# Connectors.net
KiCad netlist of a schematic drawn in Altium Designer
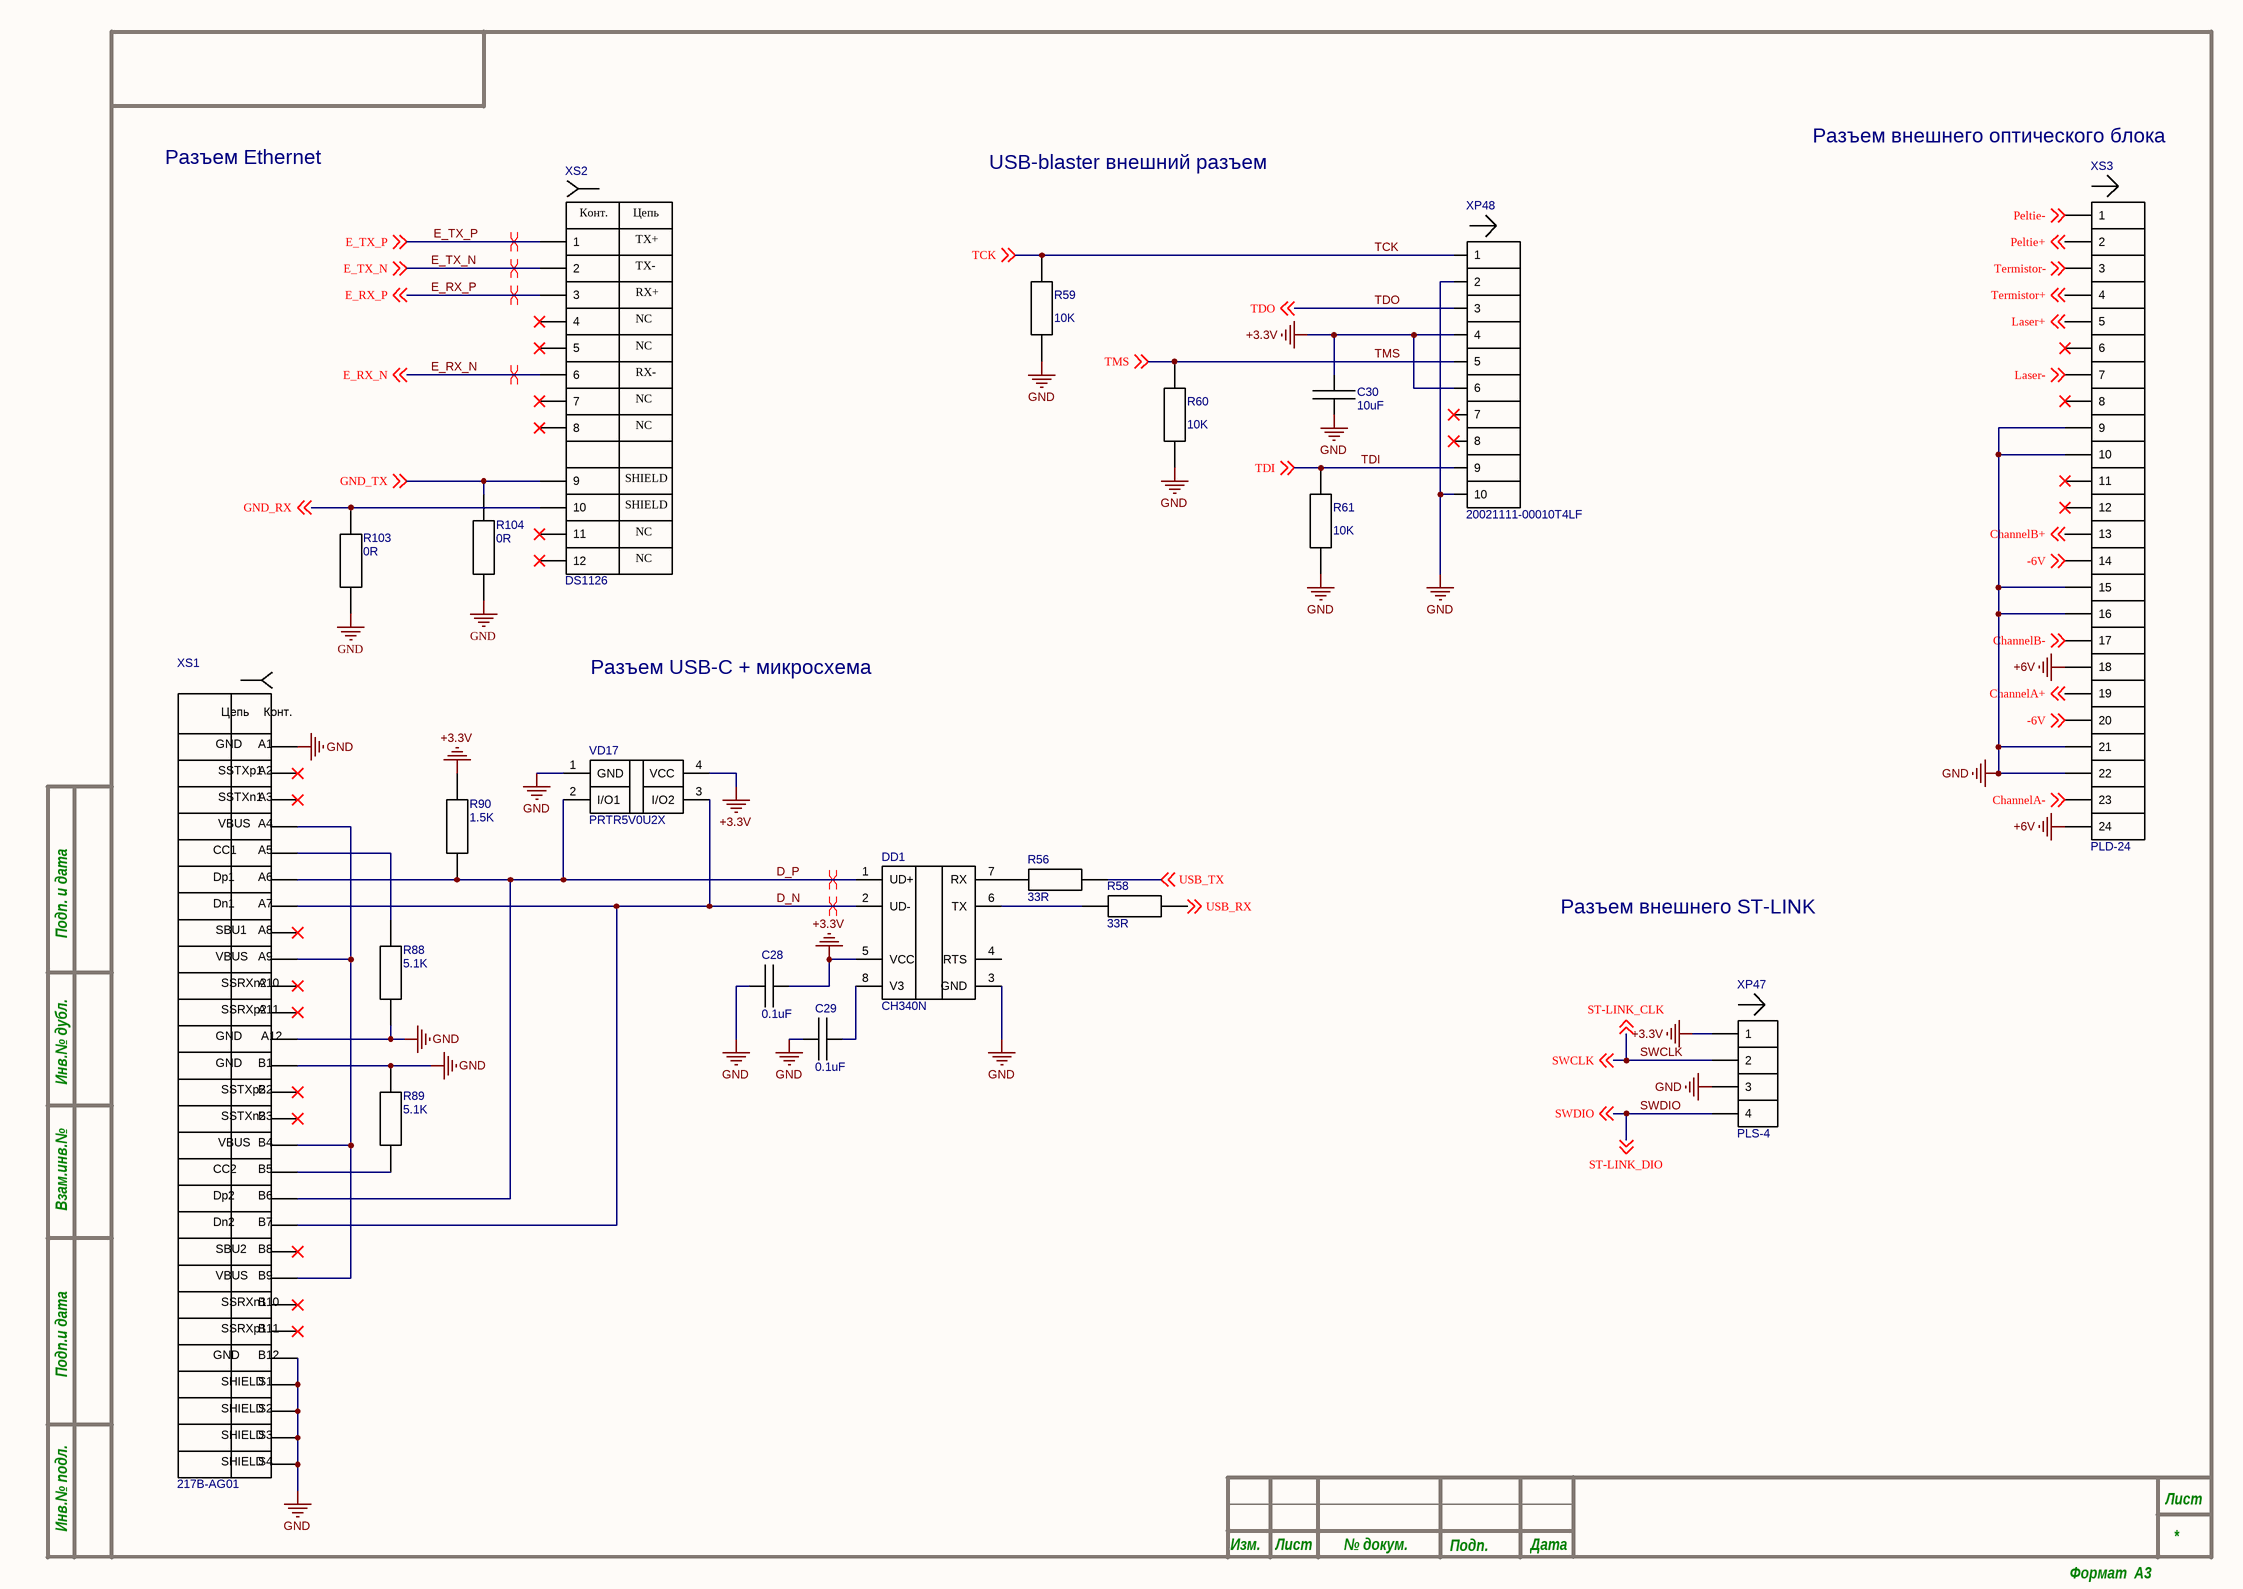
[diagram p0: Connectors — копия.SchDoc]

(export (version "E")
  (design (tool "Eeschema 10.0.6"))
  (components
    (comp (ref "C28")
      (value "0.1uF")
      (footprint "0805C")
      (description "C0805 0.1UF 10% 50V")
      (fields
        (field (name "PART NUMBER") "SMD CAP CER 0.1UF ±10% 50V X7R 0805")
        (field (name "ADDED_BY") "anton@teslatec.ru")
      )
      (libsource (lib "Test_Stand_Pergam") (part "C0805-0.1UF 10% 50V"))
    )
    (comp (ref "C29")
      (value "0.1uF")
      (footprint "0805C")
      (description "C0805 0.1UF 10% 50V")
      (fields
        (field (name "PART NUMBER") "SMD CAP CER 0.1UF ±10% 50V X7R 0805")
        (field (name "ADDED_BY") "anton@teslatec.ru")
      )
      (libsource (lib "Test_Stand_Pergam") (part "C0805-0.1UF 10% 50V"))
    )
    (comp (ref "C30")
      (value "10uF")
      (footprint "0402C")
      (description "C0402-10UF 10% 10V")
      (fields
        (field (name "PART NUMBER") "SMD CAP CER 10UF ±10% 10V X5R 0402")
        (field (name "ADDED_BY") "Rutel@Mail.ru")
      )
      (libsource (lib "Test_Stand_Pergam") (part "C0402-10UF 10% 10V"))
    )
    (comp (ref "DD1")
      (value "CH340N")
      (footprint "SOP8")
      (description "USB to Serial Port Chip CH340, SOP-8")
      (fields (field (name "ADDED_BY") "irdolgopolowa@yandex.ru"))
      (libsource (lib "Test_Stand_Pergam") (part "CH340N"))
    )
    (comp (ref "R56")
      (value "33R")
      (footprint "R0402")
      (description "Resistor SMD 33R 1% 0402")
      (fields
        (field (name "PART NUMBER") "SMD RES 33R OHM 1% ±100ppm/°C 0402")
        (field (name "ADDED_BY") "Rutel@teslatec.ru")
      )
      (libsource (lib "Test_Stand_Pergam") (part "R0402-33R"))
    )
    (comp (ref "R58")
      (value "33R")
      (footprint "R0402")
      (description "Resistor SMD 33R 1% 0402")
      (fields
        (field (name "PART NUMBER") "SMD RES 33R OHM 1% ±100ppm/°C 0402")
        (field (name "ADDED_BY") "Rutel@teslatec.ru")
      )
      (libsource (lib "Test_Stand_Pergam") (part "R0402-33R"))
    )
    (comp (ref "R59")
      (value "10K")
      (footprint "R0402")
      (description "Resistor SMD 10K 1% 0402")
      (fields
        (field (name "PART NUMBER") "SMD RES 10 KOHM 1% ±100ppm/°C 0402")
        (field (name "ADDED_BY") "Rutel@teslatec.ru")
      )
      (libsource (lib "Test_Stand_Pergam") (part "R0402-10K"))
    )
    (comp (ref "R60")
      (value "10K")
      (footprint "R0402")
      (description "Resistor SMD 10K 1% 0402")
      (fields
        (field (name "PART NUMBER") "SMD RES 10 KOHM 1% ±100ppm/°C 0402")
        (field (name "ADDED_BY") "Rutel@teslatec.ru")
      )
      (libsource (lib "Test_Stand_Pergam") (part "R0402-10K"))
    )
    (comp (ref "R61")
      (value "10K")
      (footprint "R0402")
      (description "Resistor SMD 10K 1% 0402")
      (fields
        (field (name "PART NUMBER") "SMD RES 10 KOHM 1% ±100ppm/°C 0402")
        (field (name "ADDED_BY") "Rutel@teslatec.ru")
      )
      (libsource (lib "Test_Stand_Pergam") (part "R0402-10K"))
    )
    (comp (ref "R88")
      (value "5.1K")
      (footprint "R0402")
      (description "Resistor SMD 5.1K 1% 0402")
      (fields
        (field (name "PART NUMBER") "SMD RES 5.1 KOHM 1% ±100ppm/°C 0402")
        (field (name "ADDED_BY") "Rutel@teslatec.ru")
      )
      (libsource (lib "Test_Stand_Pergam") (part "R0402-5.1K"))
    )
    (comp (ref "R89")
      (value "5.1K")
      (footprint "R0402")
      (description "Resistor SMD 5.1K 1% 0402")
      (fields
        (field (name "PART NUMBER") "SMD RES 5.1 KOHM 1% ±100ppm/°C 0402")
        (field (name "ADDED_BY") "Rutel@teslatec.ru")
      )
      (libsource (lib "Test_Stand_Pergam") (part "R0402-5.1K"))
    )
    (comp (ref "R90")
      (value "1.5K")
      (footprint "R0402")
      (description "Resistor SMD 1.5K 1% 0402")
      (fields
        (field (name "PART NUMBER") "SMD RES 1.5 KOHM 1% ±100ppm/°C 0402")
        (field (name "ADDED_BY") "Rutel@teslatec.ru")
      )
      (libsource (lib "Test_Stand_Pergam") (part "R0402-1.5K"))
    )
    (comp (ref "R103")
      (value "0R")
      (footprint "R0402")
      (description "Resistor SMD 0R 1% 0402")
      (fields
        (field (name "PART NUMBER") "SMD RES 0R 0402")
        (field (name "ADDED_BY") "irdolgopolowa@yandex.ru")
      )
      (libsource (lib "Test_Stand_Pergam") (part "R0402-0R"))
    )
    (comp (ref "R104")
      (value "0R")
      (footprint "R0402")
      (description "Resistor SMD 0R 1% 0402")
      (fields
        (field (name "PART NUMBER") "SMD RES 0R 0402")
        (field (name "ADDED_BY") "irdolgopolowa@yandex.ru")
      )
      (libsource (lib "Test_Stand_Pergam") (part "R0402-0R"))
    )
    (comp (ref "VD17")
      (value "PRTR5V0U2X")
      (footprint "SOT143B")
      (description "PRTR5V0U2X, ESD(Rail-to-Rail), 1pF,  5V")
      (fields (field (name "ADDED_BY") "irdolgopolowa@yandex.ru"))
      (libsource (lib "Test_Stand_Pergam") (part "PRTR5V0U2X"))
    )
    (comp (ref "XP47")
      (value "PLS-4")
      (footprint "PLS-4")
      (description "HEADER 2.54mm")
      (fields (field (name "MATING PART") "BLS-4") (field (name "ADDED_BY") "irdolgopolowa@yandex.ru"))
      (libsource (lib "Test_Stand_Pergam") (part "PLS-4"))
    )
    (comp (ref "XP48")
      (value "20021111-00010T4LF")
      (footprint "20021111-00010T4LF")
      (description "20021111-00010T4LF. pin 10")
      (fields (field (name "ADDED_BY") "irdolgopolowa@yandex.ru"))
      (libsource (lib "Test_Stand_Pergam") (part "20021111-00010T4LF"))
    )
    (comp (ref "XS1")
      (value "217B-AG01")
      (footprint "217B-AG01")
      (description "USB Type-C, Right Angle Hybrid Type, 30u\"")
      (fields (field (name "ADDED_BY") "ridel_av@teslatec.ru"))
      (libsource (lib "Test_Stand_Pergam") (part "217B-AG01"))
    )
    (comp (ref "XS2")
      (value "DS1126")
      (footprint "DS1126")
      (description "Ethernet PCB 8/8 RJ45")
      (fields (field (name "ADDED_BY") "irdolgopolowa@yandex.ru"))
      (libsource (lib "Test_Stand_Pergam") (part "DS1126"))
    )
    (comp (ref "XS3")
      (value "PLD-24")
      (footprint "PLD-24")
      (description "Pin Header Pitch 2.54mm")
      (fields (field (name "ADDED_BY") "andrew@teslatec.ru"))
      (libsource (lib "Test_Stand_Pergam") (part "PLD-24"))
    )
  )
  (nets
    (net (code "1") (name "+3.3V") (class "Default")
      (node (ref "C28") (pin "2") (pinfunction "2_2") (pintype "passive"))
      (node (ref "C30") (pin "2") (pinfunction "2_2") (pintype "passive"))
      (node (ref "DD1") (pin "5") (pinfunction "VCC_5") (pintype "passive"))
      (node (ref "R90") (pin "2") (pinfunction "2_2") (pintype "passive"))
      (node (ref "VD17") (pin "4") (pinfunction "VCC_4") (pintype "passive"))
      (node (ref "XP47") (pin "1") (pinfunction "1_1") (pintype "passive"))
      (node (ref "XP48") (pin "4") (pinfunction "4_4") (pintype "passive"))
      (node (ref "XP48") (pin "6") (pinfunction "6_6") (pintype "passive"))
    )
    (net (code "2") (name "+6V") (class "Default")
      (node (ref "XS3") (pin "18") (pinfunction "18_18") (pintype "passive"))
      (node (ref "XS3") (pin "24") (pinfunction "24_24") (pintype "passive"))
    )
    (net (code "3") (name "-6V") (class "Default")
      (node (ref "XS3") (pin "14") (pinfunction "14_14") (pintype "passive"))
      (node (ref "XS3") (pin "20") (pinfunction "20_20") (pintype "passive"))
    )
    (net (code "4") (name "/D_N") (class "Default")
      (node (ref "DD1") (pin "2") (pinfunction "UD-_2") (pintype "passive"))
      (node (ref "VD17") (pin "3") (pinfunction "I/O2_3") (pintype "passive"))
      (node (ref "XS1") (pin "A7") (pinfunction "Dn1_A7") (pintype "passive"))
      (node (ref "XS1") (pin "B7") (pinfunction "Dn2_B7") (pintype "passive"))
    )
    (net (code "5") (name "/D_P") (class "Default")
      (node (ref "DD1") (pin "1") (pinfunction "UD+_1") (pintype "passive"))
      (node (ref "R90") (pin "1") (pinfunction "1_1") (pintype "passive"))
      (node (ref "VD17") (pin "2") (pinfunction "I/O1_2") (pintype "passive"))
      (node (ref "XS1") (pin "A6") (pinfunction "Dp1_A6") (pintype "passive"))
      (node (ref "XS1") (pin "B6") (pinfunction "Dp2_B6") (pintype "passive"))
    )
    (net (code "6") (name "ChannelA+") (class "Default")
      (node (ref "XS3") (pin "19") (pinfunction "19_19") (pintype "passive"))
    )
    (net (code "7") (name "ChannelA-") (class "Default")
      (node (ref "XS3") (pin "23") (pinfunction "23_23") (pintype "passive"))
    )
    (net (code "8") (name "ChannelB+") (class "Default")
      (node (ref "XS3") (pin "13") (pinfunction "13_13") (pintype "passive"))
    )
    (net (code "9") (name "ChannelB-") (class "Default")
      (node (ref "XS3") (pin "17") (pinfunction "17_17") (pintype "passive"))
    )
    (net (code "10") (name "E_RX_N") (class "Default")
      (node (ref "XS2") (pin "6") (pinfunction "6_6") (pintype "passive"))
    )
    (net (code "11") (name "E_RX_P") (class "Default")
      (node (ref "XS2") (pin "3") (pinfunction "3_3") (pintype "passive"))
    )
    (net (code "12") (name "E_TX_N") (class "Default")
      (node (ref "XS2") (pin "2") (pinfunction "2_2") (pintype "passive"))
    )
    (net (code "13") (name "E_TX_P") (class "Default")
      (node (ref "XS2") (pin "1") (pinfunction "1_1") (pintype "passive"))
    )
    (net (code "14") (name "GND") (class "Default")
      (node (ref "C28") (pin "1") (pinfunction "1_1") (pintype "passive"))
      (node (ref "C29") (pin "1") (pinfunction "1_1") (pintype "passive"))
      (node (ref "C30") (pin "1") (pinfunction "1_1") (pintype "passive"))
      (node (ref "DD1") (pin "3") (pinfunction "GND_3") (pintype "passive"))
      (node (ref "R103") (pin "1") (pinfunction "1_1") (pintype "passive"))
      (node (ref "R104") (pin "1") (pinfunction "1_1") (pintype "passive"))
      (node (ref "R59") (pin "1") (pinfunction "1_1") (pintype "passive"))
      (node (ref "R60") (pin "1") (pinfunction "1_1") (pintype "passive"))
      (node (ref "R61") (pin "1") (pinfunction "1_1") (pintype "passive"))
      (node (ref "R88") (pin "1") (pinfunction "1_1") (pintype "passive"))
      (node (ref "R89") (pin "2") (pinfunction "2_2") (pintype "passive"))
      (node (ref "VD17") (pin "1") (pinfunction "GND_1") (pintype "passive"))
      (node (ref "XP47") (pin "3") (pinfunction "3_3") (pintype "passive"))
      (node (ref "XP48") (pin "10") (pinfunction "10_10") (pintype "passive"))
      (node (ref "XP48") (pin "2") (pinfunction "2_2") (pintype "passive"))
      (node (ref "XS1") (pin "A1") (pinfunction "GND_A1") (pintype "passive"))
      (node (ref "XS1") (pin "A12") (pinfunction "GND_A12") (pintype "passive"))
      (node (ref "XS1") (pin "B1") (pinfunction "GND_B1") (pintype "passive"))
      (node (ref "XS1") (pin "B12") (pinfunction "GND_B12") (pintype "passive"))
      (node (ref "XS1") (pin "S1") (pinfunction "SHIELD_S1") (pintype "passive"))
      (node (ref "XS1") (pin "S2") (pinfunction "SHIELD_S2") (pintype "passive"))
      (node (ref "XS1") (pin "S3") (pinfunction "SHIELD_S3") (pintype "passive"))
      (node (ref "XS1") (pin "S4") (pinfunction "SHIELD_S4") (pintype "passive"))
      (node (ref "XS3") (pin "10") (pinfunction "10_10") (pintype "passive"))
      (node (ref "XS3") (pin "15") (pinfunction "15_15") (pintype "passive"))
      (node (ref "XS3") (pin "16") (pinfunction "16_16") (pintype "passive"))
      (node (ref "XS3") (pin "21") (pinfunction "21_21") (pintype "passive"))
      (node (ref "XS3") (pin "22") (pinfunction "22_22") (pintype "passive"))
      (node (ref "XS3") (pin "9") (pinfunction "9_9") (pintype "passive"))
    )
    (net (code "15") (name "GND_RX") (class "Default")
      (node (ref "R103") (pin "2") (pinfunction "2_2") (pintype "passive"))
      (node (ref "XS2") (pin "10") (pinfunction "10_10") (pintype "passive"))
    )
    (net (code "16") (name "GND_TX") (class "Default")
      (node (ref "R104") (pin "2") (pinfunction "2_2") (pintype "passive"))
      (node (ref "XS2") (pin "9") (pinfunction "9_9") (pintype "passive"))
    )
    (net (code "17") (name "Laser+") (class "Default")
      (node (ref "XS3") (pin "5") (pinfunction "5_5") (pintype "passive"))
    )
    (net (code "18") (name "Laser-") (class "Default")
      (node (ref "XS3") (pin "7") (pinfunction "7_7") (pintype "passive"))
    )
    (net (code "19") (name "Net-(DD1-RX)") (class "Default")
      (node (ref "DD1") (pin "7") (pinfunction "RX_7") (pintype "passive"))
      (node (ref "R56") (pin "1") (pinfunction "1_1") (pintype "passive"))
    )
    (net (code "20") (name "Net-(DD1-TX)") (class "Default")
      (node (ref "DD1") (pin "6") (pinfunction "TX_6") (pintype "passive"))
      (node (ref "R58") (pin "1") (pinfunction "1_1") (pintype "passive"))
    )
    (net (code "21") (name "Net-(DD1-V3)") (class "Default")
      (node (ref "C29") (pin "2") (pinfunction "2_2") (pintype "passive"))
      (node (ref "DD1") (pin "8") (pinfunction "V3_8") (pintype "passive"))
    )
    (net (code "22") (name "Net-(XS1-CC1)") (class "Default")
      (node (ref "R88") (pin "2") (pinfunction "2_2") (pintype "passive"))
      (node (ref "XS1") (pin "A5") (pinfunction "CC1_A5") (pintype "passive"))
    )
    (net (code "23") (name "Net-(XS1-CC2)") (class "Default")
      (node (ref "R89") (pin "1") (pinfunction "1_1") (pintype "passive"))
      (node (ref "XS1") (pin "B5") (pinfunction "CC2_B5") (pintype "passive"))
    )
    (net (code "24") (name "Net-(XS1-VBUS-PadA4)") (class "Default")
      (node (ref "XS1") (pin "A4") (pinfunction "VBUS_A4") (pintype "passive"))
      (node (ref "XS1") (pin "A9") (pinfunction "VBUS_A9") (pintype "passive"))
      (node (ref "XS1") (pin "B4") (pinfunction "VBUS_B4") (pintype "passive"))
      (node (ref "XS1") (pin "B9") (pinfunction "VBUS_B9") (pintype "passive"))
    )
    (net (code "25") (name "Peltie+") (class "Default")
      (node (ref "XS3") (pin "2") (pinfunction "2_2") (pintype "passive"))
    )
    (net (code "26") (name "Peltie-") (class "Default")
      (node (ref "XS3") (pin "1") (pinfunction "1_1") (pintype "passive"))
    )
    (net (code "27") (name "ST-LINK_CLK") (class "Default")
      (node (ref "XP47") (pin "2") (pinfunction "2_2") (pintype "passive"))
    )
    (net (code "28") (name "ST-LINK_DIO") (class "Default")
      (node (ref "XP47") (pin "4") (pinfunction "4_4") (pintype "passive"))
    )
    (net (code "29") (name "TCK") (class "Default")
      (node (ref "R59") (pin "2") (pinfunction "2_2") (pintype "passive"))
      (node (ref "XP48") (pin "1") (pinfunction "1_1") (pintype "passive"))
    )
    (net (code "30") (name "TDI") (class "Default")
      (node (ref "R61") (pin "2") (pinfunction "2_2") (pintype "passive"))
      (node (ref "XP48") (pin "9") (pinfunction "9_9") (pintype "passive"))
    )
    (net (code "31") (name "TDO") (class "Default")
      (node (ref "XP48") (pin "3") (pinfunction "3_3") (pintype "passive"))
    )
    (net (code "32") (name "TMS") (class "Default")
      (node (ref "R60") (pin "2") (pinfunction "2_2") (pintype "passive"))
      (node (ref "XP48") (pin "5") (pinfunction "5_5") (pintype "passive"))
    )
    (net (code "33") (name "Termistor+") (class "Default")
      (node (ref "XS3") (pin "4") (pinfunction "4_4") (pintype "passive"))
    )
    (net (code "34") (name "Termistor-") (class "Default")
      (node (ref "XS3") (pin "3") (pinfunction "3_3") (pintype "passive"))
    )
    (net (code "35") (name "USB_RX") (class "Default")
      (node (ref "R58") (pin "2") (pinfunction "2_2") (pintype "passive"))
    )
    (net (code "36") (name "USB_TX") (class "Default")
      (node (ref "R56") (pin "2") (pinfunction "2_2") (pintype "passive"))
    )
    (net (code "37") (name "unconnected-(DD1-RTS-Pad4)") (class "Default")
      (node (ref "DD1") (pin "4") (pinfunction "RTS_4") (pintype "passive"))
    )
    (net (code "38") (name "unconnected-(XP48-Pad7)") (class "Default")
      (node (ref "XP48") (pin "7") (pinfunction "7_7") (pintype "passive+no_connect"))
    )
    (net (code "39") (name "unconnected-(XP48-Pad8)") (class "Default")
      (node (ref "XP48") (pin "8") (pinfunction "8_8") (pintype "passive+no_connect"))
    )
    (net (code "40") (name "unconnected-(XS1-SBU1-PadA8)") (class "Default")
      (node (ref "XS1") (pin "A8") (pinfunction "SBU1_A8") (pintype "passive+no_connect"))
    )
    (net (code "41") (name "unconnected-(XS1-SBU2-PadB8)") (class "Default")
      (node (ref "XS1") (pin "B8") (pinfunction "SBU2_B8") (pintype "passive+no_connect"))
    )
    (net (code "42") (name "unconnected-(XS1-SSRXn1-PadB10)") (class "Default")
      (node (ref "XS1") (pin "B10") (pinfunction "SSRXn1_B10") (pintype "passive+no_connect"))
    )
    (net (code "43") (name "unconnected-(XS1-SSRXn2-PadA10)") (class "Default")
      (node (ref "XS1") (pin "A10") (pinfunction "SSRXn2_A10") (pintype "passive+no_connect"))
    )
    (net (code "44") (name "unconnected-(XS1-SSRXp1-PadB11)") (class "Default")
      (node (ref "XS1") (pin "B11") (pinfunction "SSRXp1_B11") (pintype "passive+no_connect"))
    )
    (net (code "45") (name "unconnected-(XS1-SSRXp2-PadA11)") (class "Default")
      (node (ref "XS1") (pin "A11") (pinfunction "SSRXp2_A11") (pintype "passive+no_connect"))
    )
    (net (code "46") (name "unconnected-(XS1-SSTXn1-PadA3)") (class "Default")
      (node (ref "XS1") (pin "A3") (pinfunction "SSTXn1_A3") (pintype "passive+no_connect"))
    )
    (net (code "47") (name "unconnected-(XS1-SSTXn2-PadB3)") (class "Default")
      (node (ref "XS1") (pin "B3") (pinfunction "SSTXn2_B3") (pintype "passive+no_connect"))
    )
    (net (code "48") (name "unconnected-(XS1-SSTXp1-PadA2)") (class "Default")
      (node (ref "XS1") (pin "A2") (pinfunction "SSTXp1_A2") (pintype "passive+no_connect"))
    )
    (net (code "49") (name "unconnected-(XS1-SSTXp2-PadB2)") (class "Default")
      (node (ref "XS1") (pin "B2") (pinfunction "SSTXp2_B2") (pintype "passive+no_connect"))
    )
    (net (code "50") (name "unconnected-(XS2-Pad4)") (class "Default")
      (node (ref "XS2") (pin "4") (pinfunction "4_4") (pintype "passive+no_connect"))
    )
    (net (code "51") (name "unconnected-(XS2-Pad5)") (class "Default")
      (node (ref "XS2") (pin "5") (pinfunction "5_5") (pintype "passive+no_connect"))
    )
    (net (code "52") (name "unconnected-(XS2-Pad7)") (class "Default")
      (node (ref "XS2") (pin "7") (pinfunction "7_7") (pintype "passive+no_connect"))
    )
    (net (code "53") (name "unconnected-(XS2-Pad8)") (class "Default")
      (node (ref "XS2") (pin "8") (pinfunction "8_8") (pintype "passive+no_connect"))
    )
    (net (code "54") (name "unconnected-(XS2-Pad11)") (class "Default")
      (node (ref "XS2") (pin "11") (pinfunction "11_11") (pintype "passive+no_connect"))
    )
    (net (code "55") (name "unconnected-(XS2-Pad12)") (class "Default")
      (node (ref "XS2") (pin "12") (pinfunction "12_12") (pintype "passive+no_connect"))
    )
    (net (code "56") (name "unconnected-(XS3-Pad6)") (class "Default")
      (node (ref "XS3") (pin "6") (pinfunction "6_6") (pintype "passive+no_connect"))
    )
    (net (code "57") (name "unconnected-(XS3-Pad8)") (class "Default")
      (node (ref "XS3") (pin "8") (pinfunction "8_8") (pintype "passive+no_connect"))
    )
    (net (code "58") (name "unconnected-(XS3-Pad11)") (class "Default")
      (node (ref "XS3") (pin "11") (pinfunction "11_11") (pintype "passive+no_connect"))
    )
    (net (code "59") (name "unconnected-(XS3-Pad12)") (class "Default")
      (node (ref "XS3") (pin "12") (pinfunction "12_12") (pintype "passive+no_connect"))
    )
  )
)
